# MiP_D1_mini_Pack.net
KiCad netlist of a schematic drawn in EAGLE
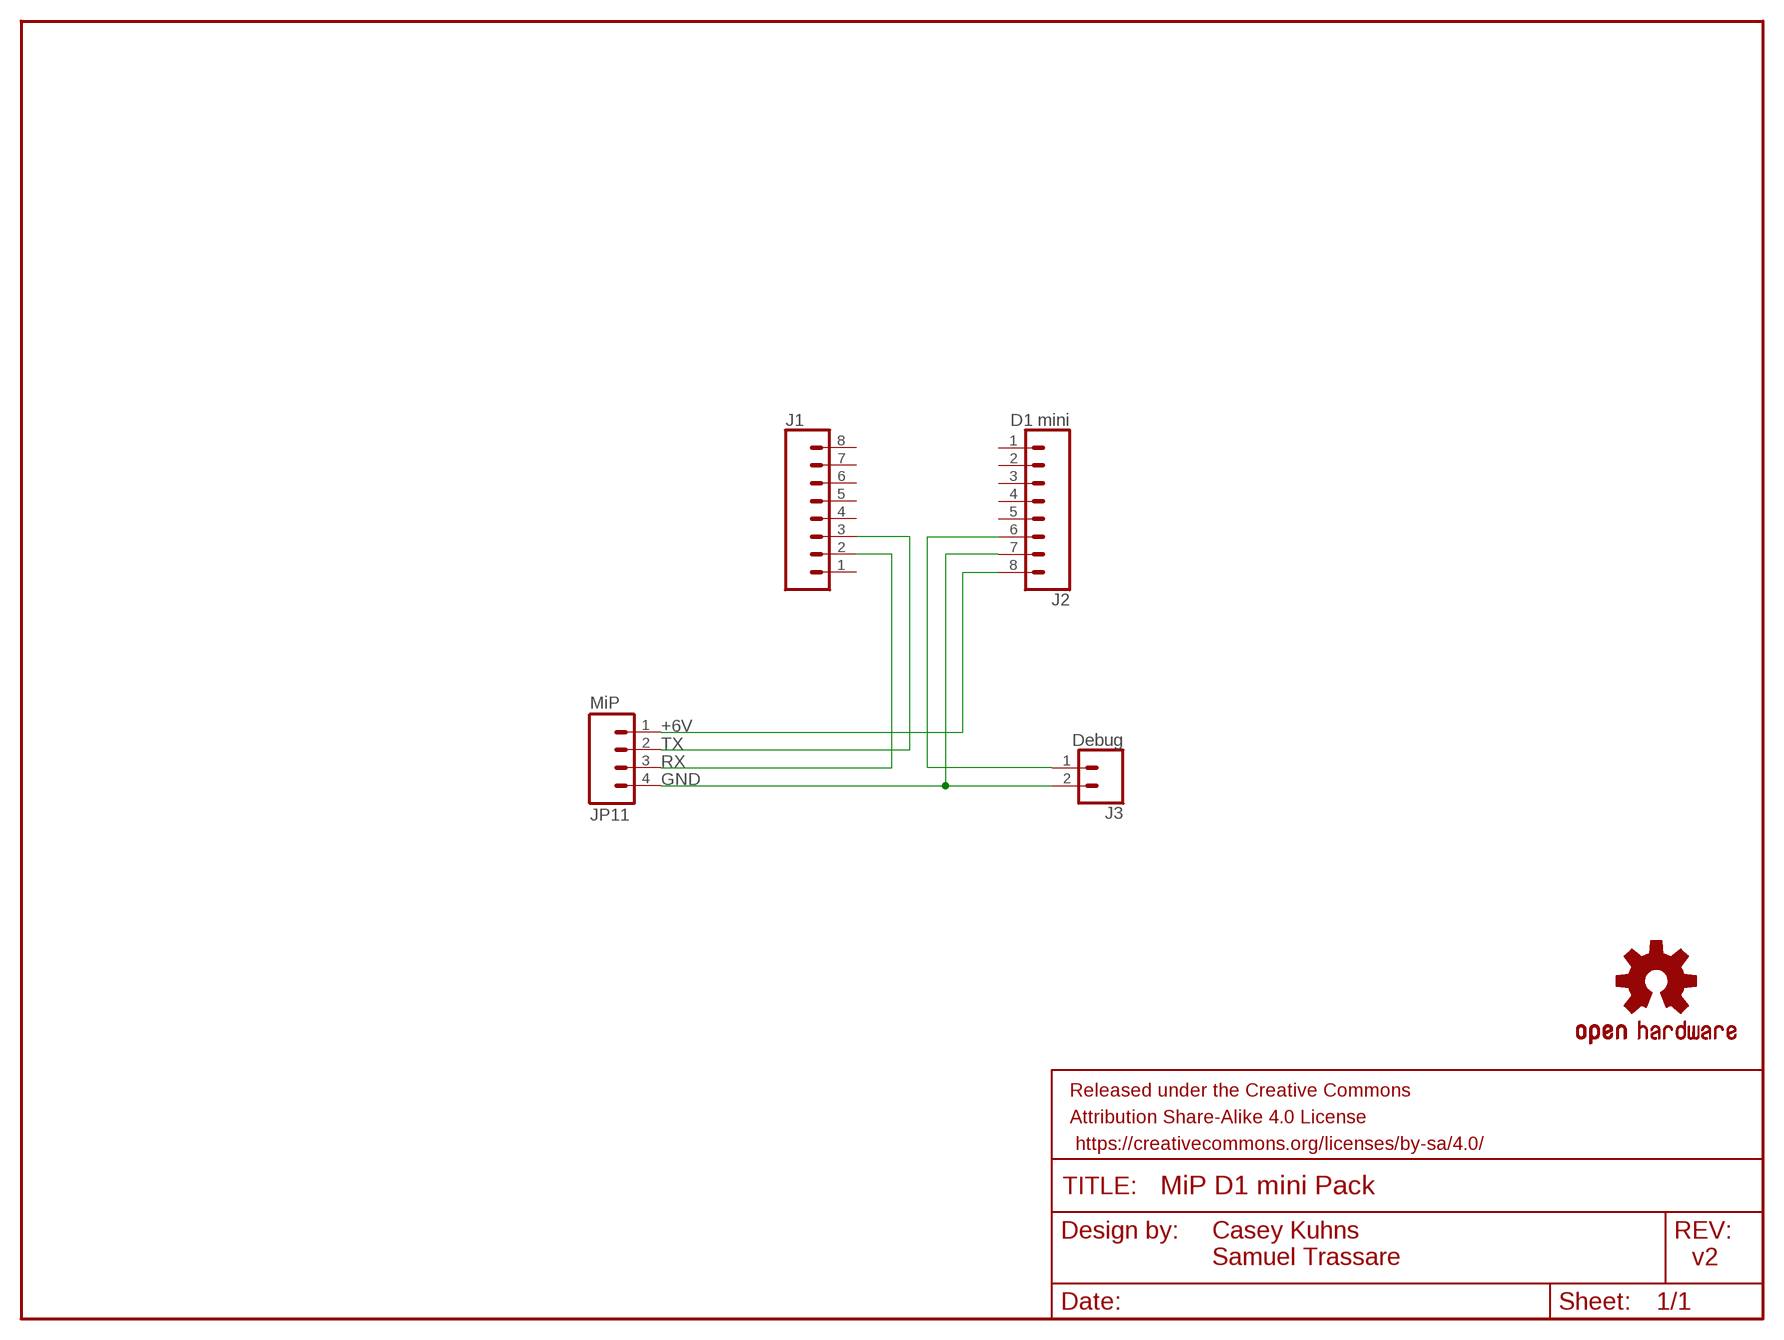
[diagram p0: schematic, sheet 1]

(export (version "E")
  (design (tool "Eeschema 10.0.6"))
  (components
    (comp (ref "FRAME1")
      (value "FRAME-LETTER")
      (footprint "eagle-import:CREATIVE_COMMONS")
      (libsource (lib "eagle-import") (part "FRAME-LETTER"))
    )
    (comp (ref "J1")
      (value "CONN_08\"")
      (footprint "eagle-import:1X08")
      (libsource (lib "eagle-import") (part "CONN_08{dblquote}"))
    )
    (comp (ref "J2")
      (value "D1 mini")
      (footprint "eagle-import:1X08")
      (libsource (lib "eagle-import") (part "CONN_08{dblquote}"))
    )
    (comp (ref "J3")
      (value "Debug")
      (footprint "eagle-import:1X02_RA_PTH_FEMALE")
      (libsource (lib "eagle-import") (part "CONN_02PTH_RA_FEMALE"))
    )
    (comp (ref "JP11")
      (value "MiP")
      (footprint "eagle-import:1X04-1.5MM_JST")
      (libsource (lib "eagle-import") (part "M04JST"))
    )
    (comp (ref "LOGO2")
      (value "OSHW-LOGOS")
      (footprint "eagle-import:OSHW-LOGO-S")
      (libsource (lib "eagle-import") (part "OSHW-LOGOS"))
    )
  )
  (nets
    (net (code "1") (name "/+6V") (class "Default")
      (node (ref "J2") (pin "8") (pinfunction "8_8") (pintype "passive"))
      (node (ref "JP11") (pin "1") (pinfunction "1_1") (pintype "passive"))
    )
    (net (code "2") (name "/GND") (class "Default")
      (node (ref "J2") (pin "7") (pinfunction "7_7") (pintype "passive"))
      (node (ref "J3") (pin "2") (pinfunction "2_2") (pintype "passive"))
      (node (ref "JP11") (pin "4") (pinfunction "4_4") (pintype "passive"))
    )
    (net (code "3") (name "/RX") (class "Default")
      (node (ref "J1") (pin "2") (pinfunction "2_2") (pintype "passive"))
      (node (ref "JP11") (pin "3") (pinfunction "3_3") (pintype "passive"))
    )
    (net (code "4") (name "/TX") (class "Default")
      (node (ref "J1") (pin "3") (pinfunction "3_3") (pintype "passive"))
      (node (ref "JP11") (pin "2") (pinfunction "2_2") (pintype "passive"))
    )
    (net (code "5") (name "Net-(J2-Pad6)") (class "Default")
      (node (ref "J2") (pin "6") (pinfunction "6_6") (pintype "passive"))
      (node (ref "J3") (pin "1") (pinfunction "1_1") (pintype "passive"))
    )
    (net (code "6") (name "unconnected-(J1-Pad1)") (class "Default")
      (node (ref "J1") (pin "1") (pinfunction "1_1") (pintype "passive"))
    )
    (net (code "7") (name "unconnected-(J1-Pad4)") (class "Default")
      (node (ref "J1") (pin "4") (pinfunction "4_4") (pintype "passive"))
    )
    (net (code "8") (name "unconnected-(J1-Pad5)") (class "Default")
      (node (ref "J1") (pin "5") (pinfunction "5_5") (pintype "passive"))
    )
    (net (code "9") (name "unconnected-(J1-Pad6)") (class "Default")
      (node (ref "J1") (pin "6") (pinfunction "6_6") (pintype "passive"))
    )
    (net (code "10") (name "unconnected-(J1-Pad7)") (class "Default")
      (node (ref "J1") (pin "7") (pinfunction "7_7") (pintype "passive"))
    )
    (net (code "11") (name "unconnected-(J1-Pad8)") (class "Default")
      (node (ref "J1") (pin "8") (pinfunction "8_8") (pintype "passive"))
    )
    (net (code "12") (name "unconnected-(J2-Pad1)") (class "Default")
      (node (ref "J2") (pin "1") (pinfunction "1_1") (pintype "passive"))
    )
    (net (code "13") (name "unconnected-(J2-Pad2)") (class "Default")
      (node (ref "J2") (pin "2") (pinfunction "2_2") (pintype "passive"))
    )
    (net (code "14") (name "unconnected-(J2-Pad3)") (class "Default")
      (node (ref "J2") (pin "3") (pinfunction "3_3") (pintype "passive"))
    )
    (net (code "15") (name "unconnected-(J2-Pad4)") (class "Default")
      (node (ref "J2") (pin "4") (pinfunction "4_4") (pintype "passive"))
    )
    (net (code "16") (name "unconnected-(J2-Pad5)") (class "Default")
      (node (ref "J2") (pin "5") (pinfunction "5_5") (pintype "passive"))
    )
  )
)
